# SCH__MainProcessor.net
KiCad netlist of a schematic drawn in Altium Designer
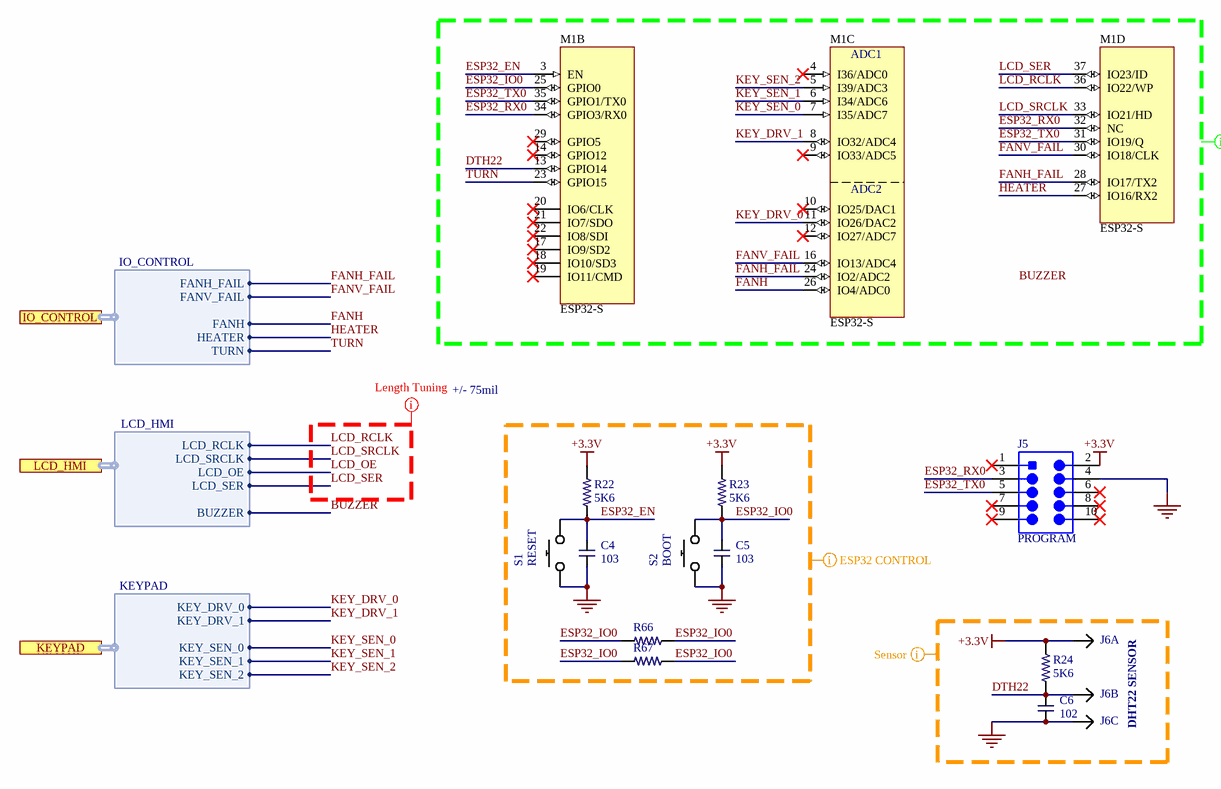
[diagram p0: [SCH]_MainProcessor.SchDoc]

(export (version "E")
  (design (tool "Eeschema 10.0.6"))
  (components
    (comp (ref "C4")
      (value "103")
      (footprint "CAP-SMD-0805")
      (description "Non-polar capacitor")
      (libsource (lib "TOAN_VERSION_1_0") (part "Cap-Non-SMD"))
    )
    (comp (ref "C5")
      (value "103")
      (footprint "CAP-SMD-0805")
      (description "Non-polar capacitor")
      (libsource (lib "TOAN_VERSION_1_0") (part "Cap-Non-SMD"))
    )
    (comp (ref "C6")
      (value "102")
      (footprint "CAP-SMD-0805")
      (description "Non-polar capacitor")
      (libsource (lib "TOAN_VERSION_1_0") (part "Cap-Non-SMD"))
    )
    (comp (ref "J5")
      (value "PROGRAM")
      (footprint "IDC10")
      (description "Male Box Header WR-BHD, THT, Vertical, pitch 2.54 mm, 10 pins")
      (libsource (lib "TOAN_VERSION_1_0") (part "IDE_5X2"))
    )
    (comp (ref "J6") (value "DHT22") (footprint "KF3/5.08") (libsource (lib "TOAN_VERSION_1_0") (part "JP3")))
    (comp (ref "M1")
      (value "ESP32-S")
      (footprint "ESP32-S-Footprint")
      (description "Tensilica Xtensa LX6 microprocessor @ 160 or 240 MHz · 320 KiB SRAM")
      (libsource (lib "TOAN_VERSION_1_0") (part "ESP32-S"))
    )
    (comp (ref "R22")
      (value "5K6")
      (footprint "RES-SMD-0805")
      (description "Chip Resistor, 0805, 1%, 1/8 W")
      (fields (field (name "Comment") "R0805"))
      (libsource (lib "TOAN_VERSION_1_0") (part "RES"))
    )
    (comp (ref "R23")
      (value "5K6")
      (footprint "RES-SMD-0805")
      (description "Chip Resistor, 0805, 1%, 1/8 W")
      (fields (field (name "Comment") "R0805"))
      (libsource (lib "TOAN_VERSION_1_0") (part "RES"))
    )
    (comp (ref "R24")
      (value "5K6")
      (footprint "RES-SMD-0805")
      (description "Chip Resistor, 0805, 1%, 1/8 W")
      (fields (field (name "Comment") "R0805"))
      (libsource (lib "TOAN_VERSION_1_0") (part "RES"))
    )
    (comp (ref "R66")
      (value "R0805")
      (footprint "RES-SMD-0805")
      (description "Chip Resistor, 0805, 1%, 1/8 W")
      (libsource (lib "TOAN_VERSION_1_0") (part "RES"))
    )
    (comp (ref "R67")
      (value "R0805")
      (footprint "RES-SMD-0805")
      (description "Chip Resistor, 0805, 1%, 1/8 W")
      (libsource (lib "TOAN_VERSION_1_0") (part "RES"))
    )
    (comp (ref "S1")
      (value "RESET")
      (footprint "TL3342F260QG")
      (description "SWITCH TACTILE SPST-NO 0.05A 12V")
      (fields (field (name "MANUFACTURER PART NUMBER") "TL3342F260QG"))
      (libsource (lib "TOAN_VERSION_1_0") (part "SWITCH TACTILE SPST"))
    )
    (comp (ref "S2")
      (value "BOOT")
      (footprint "TL3342F260QG")
      (description "SWITCH TACTILE SPST-NO 0.05A 12V")
      (fields (field (name "MANUFACTURER PART NUMBER") "TL3342F260QG"))
      (libsource (lib "TOAN_VERSION_1_0") (part "SWITCH TACTILE SPST"))
    )
  )
  (nets
    (net (code "4") (name "+3.3V") (class "Default")
      (node (ref "J5") (pin "2") (pinfunction "2_2") (pintype "passive"))
      (node (ref "J6") (pin "1") (pinfunction "1_1") (pintype "passive"))
      (node (ref "R22") (pin "2") (pintype "passive"))
      (node (ref "R23") (pin "2") (pintype "passive"))
      (node (ref "R24") (pin "2") (pintype "passive"))
    )
    (net (code "6") (name "/DTH22") (class "Default")
      (node (ref "C6") (pin "2") (pinfunction "2_2") (pintype "passive"))
      (node (ref "J6") (pin "2") (pinfunction "2_2") (pintype "passive"))
      (node (ref "M1") (pin "13") (pinfunction "GPIO14_13") (pintype "bidirectional"))
      (node (ref "R24") (pin "1") (pintype "passive"))
    )
    (net (code "7") (name "/ESP32_EN") (class "Default")
      (node (ref "C4") (pin "2") (pinfunction "2_2") (pintype "passive"))
      (node (ref "M1") (pin "3") (pinfunction "EN_3") (pintype "input"))
      (node (ref "R22") (pin "1") (pintype "passive"))
      (node (ref "S1") (pin "2") (pinfunction "2_2") (pintype "passive"))
    )
    (net (code "8") (name "/ESP32_IO0") (class "Default")
      (node (ref "C5") (pin "2") (pinfunction "2_2") (pintype "passive"))
      (node (ref "M1") (pin "25") (pinfunction "GPIO0_25") (pintype "bidirectional"))
      (node (ref "R23") (pin "1") (pintype "passive"))
      (node (ref "R66") (pin "1") (pintype "passive"))
      (node (ref "R66") (pin "2") (pintype "passive"))
      (node (ref "R67") (pin "1") (pintype "passive"))
      (node (ref "R67") (pin "2") (pintype "passive"))
      (node (ref "S2") (pin "2") (pinfunction "2_2") (pintype "passive"))
    )
    (net (code "9") (name "/ESP32_RX0") (class "Default")
      (node (ref "J5") (pin "3") (pinfunction "3_3") (pintype "passive"))
      (node (ref "M1") (pin "32") (pinfunction "NC_32") (pintype "bidirectional"))
      (node (ref "M1") (pin "34") (pinfunction "GPIO3/RX0_34") (pintype "bidirectional"))
    )
    (net (code "10") (name "/ESP32_TX0") (class "Default")
      (node (ref "J5") (pin "5") (pinfunction "5_5") (pintype "passive"))
      (node (ref "M1") (pin "31") (pinfunction "IO19/Q_31") (pintype "bidirectional"))
      (node (ref "M1") (pin "35") (pinfunction "GPIO1/TX0_35") (pintype "bidirectional"))
    )
    (net (code "11") (name "/FANH") (class "Default")
      (node (ref "M1") (pin "26") (pinfunction "IO4/ADC0_26") (pintype "bidirectional"))
    )
    (net (code "12") (name "/FANH_FAIL") (class "Default")
      (node (ref "M1") (pin "24") (pinfunction "IO2/ADC2_24") (pintype "bidirectional"))
      (node (ref "M1") (pin "28") (pinfunction "IO17/TX2_28") (pintype "bidirectional"))
    )
    (net (code "13") (name "/FANV_FAIL") (class "Default")
      (node (ref "M1") (pin "16") (pinfunction "IO13/ADC4_16") (pintype "bidirectional"))
      (node (ref "M1") (pin "30") (pinfunction "IO18/CLK_30") (pintype "bidirectional"))
    )
    (net (code "14") (name "/HEATER") (class "Default")
      (node (ref "M1") (pin "27") (pinfunction "IO16/RX2_27") (pintype "bidirectional"))
    )
    (net (code "15") (name "/KEY_DRV_0") (class "Default")
      (node (ref "M1") (pin "11") (pinfunction "IO26/DAC2_11") (pintype "bidirectional"))
    )
    (net (code "16") (name "/KEY_DRV_1") (class "Default")
      (node (ref "M1") (pin "8") (pinfunction "IO32/ADC4_8") (pintype "bidirectional"))
    )
    (net (code "17") (name "/KEY_SEN_0") (class "Default")
      (node (ref "M1") (pin "7") (pinfunction "I35/ADC7_7") (pintype "input"))
    )
    (net (code "18") (name "/KEY_SEN_1") (class "Default")
      (node (ref "M1") (pin "6") (pinfunction "I34/ADC6_6") (pintype "input"))
    )
    (net (code "19") (name "/KEY_SEN_2") (class "Default")
      (node (ref "M1") (pin "5") (pinfunction "I39/ADC3_5") (pintype "input"))
    )
    (net (code "21") (name "/LCD_RCLK") (class "Default")
      (node (ref "M1") (pin "36") (pinfunction "IO22/WP_36") (pintype "bidirectional"))
    )
    (net (code "22") (name "/LCD_SER") (class "Default")
      (node (ref "M1") (pin "37") (pinfunction "IO23/ID_37") (pintype "bidirectional"))
    )
    (net (code "23") (name "/LCD_SRCLK") (class "Default")
      (node (ref "M1") (pin "33") (pinfunction "IO21/HD_33") (pintype "bidirectional"))
    )
    (net (code "24") (name "/TURN") (class "Default")
      (node (ref "M1") (pin "23") (pinfunction "GPIO15_23") (pintype "bidirectional"))
    )
    (net (code "28") (name "GND") (class "Default")
      (node (ref "C4") (pin "1") (pinfunction "1_1") (pintype "passive"))
      (node (ref "C5") (pin "1") (pinfunction "1_1") (pintype "passive"))
      (node (ref "C6") (pin "1") (pinfunction "1_1") (pintype "passive"))
      (node (ref "J5") (pin "4") (pinfunction "4_4") (pintype "passive"))
      (node (ref "J6") (pin "3") (pinfunction "3_3") (pintype "passive"))
      (node (ref "S1") (pin "1") (pinfunction "1_1") (pintype "passive"))
      (node (ref "S2") (pin "1") (pinfunction "1_1") (pintype "passive"))
    )
    (net (code "29") (name "unconnected-(J5-Pad1)") (class "Default")
      (node (ref "J5") (pin "1") (pinfunction "1_1") (pintype "passive+no_connect"))
    )
    (net (code "30") (name "unconnected-(J5-Pad6)") (class "Default")
      (node (ref "J5") (pin "6") (pinfunction "6_6") (pintype "passive+no_connect"))
    )
    (net (code "31") (name "unconnected-(J5-Pad7)") (class "Default")
      (node (ref "J5") (pin "7") (pinfunction "7_7") (pintype "passive+no_connect"))
    )
    (net (code "32") (name "unconnected-(J5-Pad8)") (class "Default")
      (node (ref "J5") (pin "8") (pinfunction "8_8") (pintype "passive+no_connect"))
    )
    (net (code "33") (name "unconnected-(J5-Pad9)") (class "Default")
      (node (ref "J5") (pin "9") (pinfunction "9_9") (pintype "passive+no_connect"))
    )
    (net (code "34") (name "unconnected-(J5-Pad10)") (class "Default")
      (node (ref "J5") (pin "10") (pinfunction "10_10") (pintype "passive+no_connect"))
    )
    (net (code "35") (name "unconnected-(M1B-GPIO5-Pad29)") (class "Default")
      (node (ref "M1") (pin "29") (pinfunction "GPIO5_29") (pintype "bidirectional+no_connect"))
    )
    (net (code "36") (name "unconnected-(M1B-GPIO12-Pad14)") (class "Default")
      (node (ref "M1") (pin "14") (pinfunction "GPIO12_14") (pintype "bidirectional+no_connect"))
    )
    (net (code "37") (name "unconnected-(M1B-IO6{slash}CLK-Pad20)") (class "Default")
      (node (ref "M1") (pin "20") (pinfunction "IO6/CLK_20") (pintype "passive+no_connect"))
    )
    (net (code "38") (name "unconnected-(M1B-IO7{slash}SDO-Pad21)") (class "Default")
      (node (ref "M1") (pin "21") (pinfunction "IO7/SDO_21") (pintype "passive+no_connect"))
    )
    (net (code "39") (name "unconnected-(M1B-IO8{slash}SDI-Pad22)") (class "Default")
      (node (ref "M1") (pin "22") (pinfunction "IO8/SDI_22") (pintype "passive+no_connect"))
    )
    (net (code "40") (name "unconnected-(M1B-IO9{slash}SD2-Pad17)") (class "Default")
      (node (ref "M1") (pin "17") (pinfunction "IO9/SD2_17") (pintype "passive+no_connect"))
    )
    (net (code "41") (name "unconnected-(M1B-IO10{slash}SD3-Pad18)") (class "Default")
      (node (ref "M1") (pin "18") (pinfunction "IO10/SD3_18") (pintype "passive+no_connect"))
    )
    (net (code "42") (name "unconnected-(M1B-IO11{slash}CMD-Pad19)") (class "Default")
      (node (ref "M1") (pin "19") (pinfunction "IO11/CMD_19") (pintype "passive+no_connect"))
    )
    (net (code "43") (name "unconnected-(M1C-I36{slash}ADC0-Pad4)") (class "Default")
      (node (ref "M1") (pin "4") (pinfunction "I36/ADC0_4") (pintype "input+no_connect"))
    )
    (net (code "44") (name "unconnected-(M1C-IO25{slash}DAC1-Pad10)") (class "Default")
      (node (ref "M1") (pin "10") (pinfunction "IO25/DAC1_10") (pintype "bidirectional+no_connect"))
    )
    (net (code "45") (name "unconnected-(M1C-IO27{slash}ADC7-Pad12)") (class "Default")
      (node (ref "M1") (pin "12") (pinfunction "IO27/ADC7_12") (pintype "bidirectional+no_connect"))
    )
    (net (code "46") (name "unconnected-(M1C-IO33{slash}ADC5-Pad9)") (class "Default")
      (node (ref "M1") (pin "9") (pinfunction "IO33/ADC5_9") (pintype "bidirectional+no_connect"))
    )
  )
)
